# MEZZANINE.net
KiCad netlist of a schematic drawn in Altium Designer
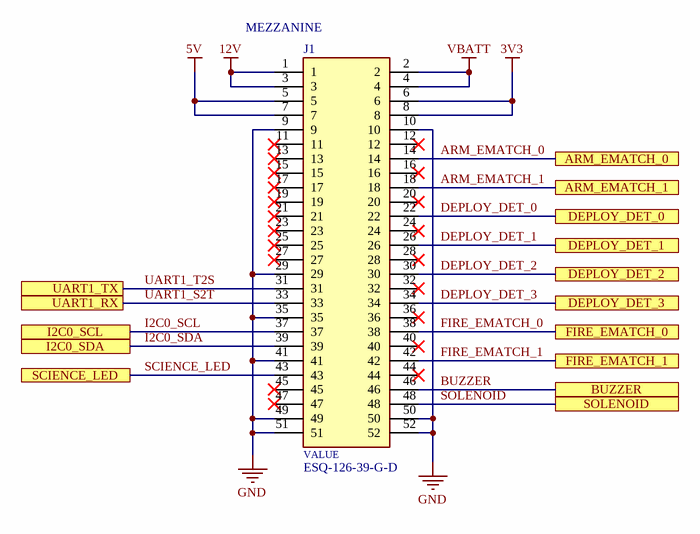
[diagram p0: MEZZANINE.SchDoc]

(export (version "E")
  (design (tool "Eeschema 10.0.6"))
  (components
    (comp (ref "J1")
      (value "ESQ-126-39-G-D")
      (footprint "SnapEDApcb:SAMTEC_ESQ-126-39-G-D")
      (description "52 Position Elevated Socket Connector Through Hole")
      (fields (field (name "DIGI-KEY_PART_NUMBER") "SAM10462-ND") (field (name "MF") "Samtec"))
      (libsource (lib "1735446-3") (part "ESQ-126-39-G-D"))
    )
  )
  (nets
    (net (code "1") (name "/ARM_EMATCH_0") (class "Default")
      (node (ref "J1") (pin "14") (pinfunction "14_14") (pintype "passive"))
    )
    (net (code "2") (name "/ARM_EMATCH_1") (class "Default")
      (node (ref "J1") (pin "18") (pinfunction "18_18") (pintype "passive"))
    )
    (net (code "3") (name "/BUZZER") (class "Default")
      (node (ref "J1") (pin "46") (pinfunction "46_46") (pintype "passive"))
    )
    (net (code "4") (name "/DEPLOY_DET_0") (class "Default")
      (node (ref "J1") (pin "22") (pinfunction "22_22") (pintype "passive"))
    )
    (net (code "5") (name "/DEPLOY_DET_1") (class "Default")
      (node (ref "J1") (pin "26") (pinfunction "26_26") (pintype "passive"))
    )
    (net (code "6") (name "/DEPLOY_DET_2") (class "Default")
      (node (ref "J1") (pin "30") (pinfunction "30_30") (pintype "passive"))
    )
    (net (code "7") (name "/DEPLOY_DET_3") (class "Default")
      (node (ref "J1") (pin "34") (pinfunction "34_34") (pintype "passive"))
    )
    (net (code "8") (name "/FIRE_EMATCH_0") (class "Default")
      (node (ref "J1") (pin "38") (pinfunction "38_38") (pintype "passive"))
    )
    (net (code "9") (name "/FIRE_EMATCH_1") (class "Default")
      (node (ref "J1") (pin "42") (pinfunction "42_42") (pintype "passive"))
    )
    (net (code "10") (name "/I2C0_SCL") (class "Default")
      (node (ref "J1") (pin "37") (pinfunction "37_37") (pintype "passive"))
    )
    (net (code "11") (name "/I2C0_SDA") (class "Default")
      (node (ref "J1") (pin "39") (pinfunction "39_39") (pintype "passive"))
    )
    (net (code "12") (name "/SCIENCE_LED") (class "Default")
      (node (ref "J1") (pin "43") (pinfunction "43_43") (pintype "passive"))
    )
    (net (code "13") (name "/SOLENOID") (class "Default")
      (node (ref "J1") (pin "48") (pinfunction "48_48") (pintype "passive"))
    )
    (net (code "14") (name "/UART1_S2T") (class "Default")
      (node (ref "J1") (pin "33") (pinfunction "33_33") (pintype "passive"))
    )
    (net (code "15") (name "/UART1_T2S") (class "Default")
      (node (ref "J1") (pin "31") (pinfunction "31_31") (pintype "passive"))
    )
    (net (code "16") (name "3V3") (class "Default")
      (node (ref "J1") (pin "6") (pinfunction "6_6") (pintype "passive"))
      (node (ref "J1") (pin "8") (pinfunction "8_8") (pintype "passive"))
    )
    (net (code "17") (name "5V") (class "Default")
      (node (ref "J1") (pin "5") (pinfunction "5_5") (pintype "passive"))
      (node (ref "J1") (pin "7") (pinfunction "7_7") (pintype "passive"))
    )
    (net (code "18") (name "12V") (class "Default")
      (node (ref "J1") (pin "1") (pinfunction "1_1") (pintype "passive"))
      (node (ref "J1") (pin "3") (pinfunction "3_3") (pintype "passive"))
    )
    (net (code "19") (name "GND") (class "Default")
      (node (ref "J1") (pin "10") (pinfunction "10_10") (pintype "passive"))
      (node (ref "J1") (pin "29") (pinfunction "29_29") (pintype "passive"))
      (node (ref "J1") (pin "35") (pinfunction "35_35") (pintype "passive"))
      (node (ref "J1") (pin "41") (pinfunction "41_41") (pintype "passive"))
      (node (ref "J1") (pin "49") (pinfunction "49_49") (pintype "passive"))
      (node (ref "J1") (pin "50") (pinfunction "50_50") (pintype "passive"))
      (node (ref "J1") (pin "51") (pinfunction "51_51") (pintype "passive"))
      (node (ref "J1") (pin "52") (pinfunction "52_52") (pintype "passive"))
      (node (ref "J1") (pin "9") (pinfunction "9_9") (pintype "passive"))
    )
    (net (code "20") (name "VBATT") (class "Default")
      (node (ref "J1") (pin "2") (pinfunction "2_2") (pintype "passive"))
      (node (ref "J1") (pin "4") (pinfunction "4_4") (pintype "passive"))
    )
    (net (code "21") (name "unconnected-(J1-Pad11)") (class "Default")
      (node (ref "J1") (pin "11") (pinfunction "11_11") (pintype "passive+no_connect"))
    )
    (net (code "22") (name "unconnected-(J1-Pad12)") (class "Default")
      (node (ref "J1") (pin "12") (pinfunction "12_12") (pintype "passive+no_connect"))
    )
    (net (code "23") (name "unconnected-(J1-Pad13)") (class "Default")
      (node (ref "J1") (pin "13") (pinfunction "13_13") (pintype "passive+no_connect"))
    )
    (net (code "24") (name "unconnected-(J1-Pad15)") (class "Default")
      (node (ref "J1") (pin "15") (pinfunction "15_15") (pintype "passive+no_connect"))
    )
    (net (code "25") (name "unconnected-(J1-Pad16)") (class "Default")
      (node (ref "J1") (pin "16") (pinfunction "16_16") (pintype "passive+no_connect"))
    )
    (net (code "26") (name "unconnected-(J1-Pad17)") (class "Default")
      (node (ref "J1") (pin "17") (pinfunction "17_17") (pintype "passive+no_connect"))
    )
    (net (code "27") (name "unconnected-(J1-Pad19)") (class "Default")
      (node (ref "J1") (pin "19") (pinfunction "19_19") (pintype "passive+no_connect"))
    )
    (net (code "28") (name "unconnected-(J1-Pad20)") (class "Default")
      (node (ref "J1") (pin "20") (pinfunction "20_20") (pintype "passive+no_connect"))
    )
    (net (code "29") (name "unconnected-(J1-Pad21)") (class "Default")
      (node (ref "J1") (pin "21") (pinfunction "21_21") (pintype "passive+no_connect"))
    )
    (net (code "30") (name "unconnected-(J1-Pad23)") (class "Default")
      (node (ref "J1") (pin "23") (pinfunction "23_23") (pintype "passive+no_connect"))
    )
    (net (code "31") (name "unconnected-(J1-Pad24)") (class "Default")
      (node (ref "J1") (pin "24") (pinfunction "24_24") (pintype "passive+no_connect"))
    )
    (net (code "32") (name "unconnected-(J1-Pad25)") (class "Default")
      (node (ref "J1") (pin "25") (pinfunction "25_25") (pintype "passive+no_connect"))
    )
    (net (code "33") (name "unconnected-(J1-Pad27)") (class "Default")
      (node (ref "J1") (pin "27") (pinfunction "27_27") (pintype "passive+no_connect"))
    )
    (net (code "34") (name "unconnected-(J1-Pad28)") (class "Default")
      (node (ref "J1") (pin "28") (pinfunction "28_28") (pintype "passive+no_connect"))
    )
    (net (code "35") (name "unconnected-(J1-Pad32)") (class "Default")
      (node (ref "J1") (pin "32") (pinfunction "32_32") (pintype "passive+no_connect"))
    )
    (net (code "36") (name "unconnected-(J1-Pad36)") (class "Default")
      (node (ref "J1") (pin "36") (pinfunction "36_36") (pintype "passive+no_connect"))
    )
    (net (code "37") (name "unconnected-(J1-Pad40)") (class "Default")
      (node (ref "J1") (pin "40") (pinfunction "40_40") (pintype "passive+no_connect"))
    )
    (net (code "38") (name "unconnected-(J1-Pad44)") (class "Default")
      (node (ref "J1") (pin "44") (pinfunction "44_44") (pintype "passive+no_connect"))
    )
    (net (code "39") (name "unconnected-(J1-Pad45)") (class "Default")
      (node (ref "J1") (pin "45") (pinfunction "45_45") (pintype "passive+no_connect"))
    )
    (net (code "40") (name "unconnected-(J1-Pad47)") (class "Default")
      (node (ref "J1") (pin "47") (pinfunction "47_47") (pintype "passive+no_connect"))
    )
  )
)
